# saturation_main.net
KiCad netlist of a schematic drawn in EAGLE
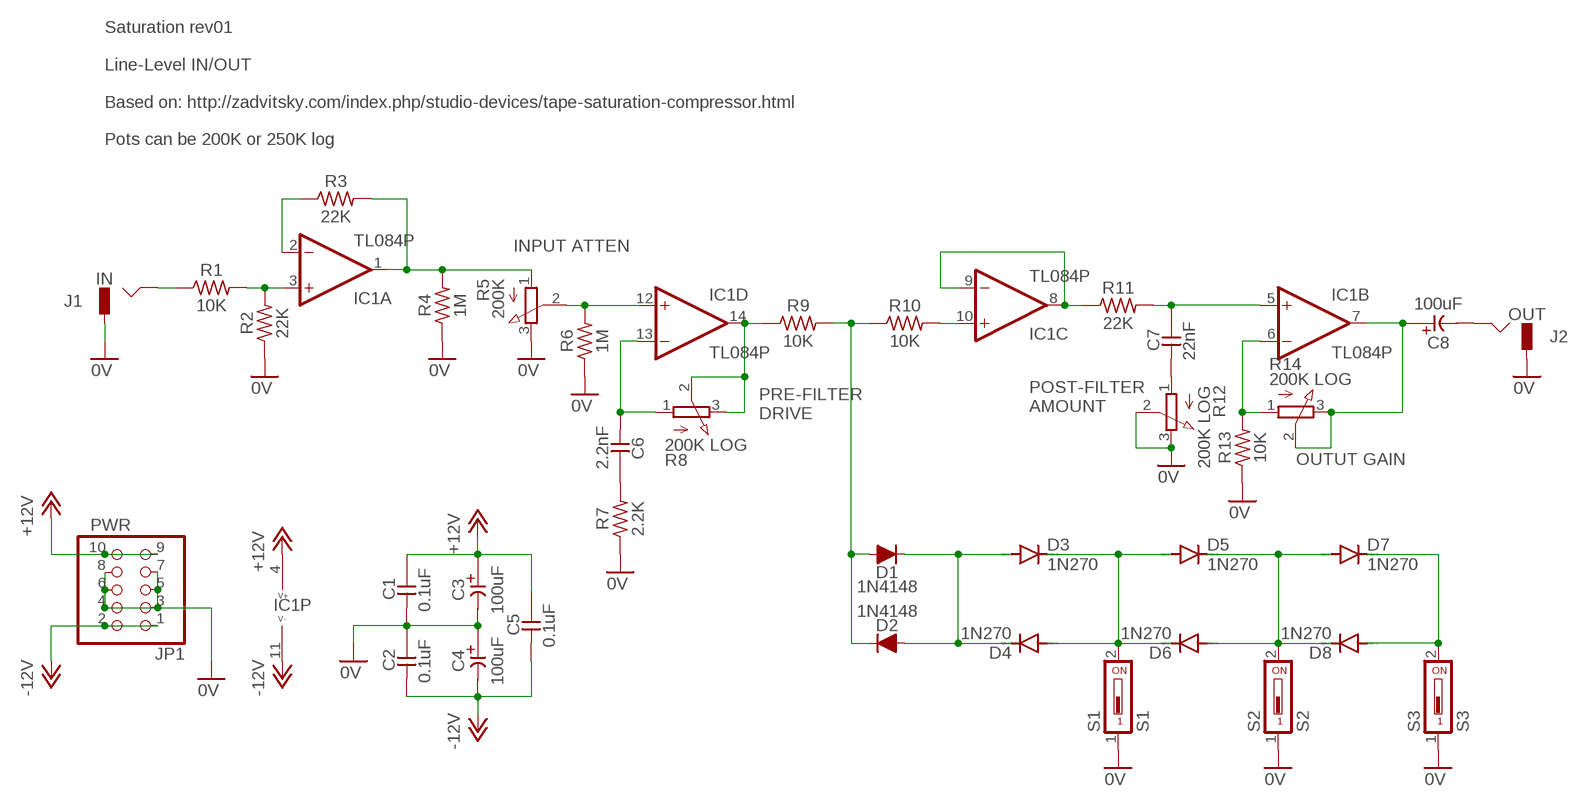
[diagram p0: schematic, sheet 1]

(export (version "E")
  (design (tool "Eeschema 10.0.6"))
  (components
    (comp (ref "C1")
      (value "0.1uF")
      (footprint "eagle-import:C025-024X044")
      (libsource (lib "eagle-import") (part "CC-US025-024X044"))
    )
    (comp (ref "C2")
      (value "0.1uF")
      (footprint "eagle-import:C025-024X044")
      (libsource (lib "eagle-import") (part "CC-US025-024X044"))
    )
    (comp (ref "C3")
      (value "100uF")
      (footprint "eagle-import:E5-8,5")
      (libsource (lib "eagle-import") (part "CE-USE5-8.5"))
    )
    (comp (ref "C4")
      (value "100uF")
      (footprint "eagle-import:E5-8,5")
      (libsource (lib "eagle-import") (part "CE-USE5-8.5"))
    )
    (comp (ref "C5")
      (value "0.1uF")
      (footprint "eagle-import:C025-024X044")
      (libsource (lib "eagle-import") (part "CC-US025-024X044"))
    )
    (comp (ref "C6")
      (value "2.2nF")
      (footprint "eagle-import:C025-024X044")
      (libsource (lib "eagle-import") (part "CC-US025-024X044"))
    )
    (comp (ref "C7")
      (value "22nF")
      (footprint "eagle-import:C025-024X044")
      (libsource (lib "eagle-import") (part "CC-US025-024X044"))
    )
    (comp (ref "C8")
      (value "100uF")
      (footprint "eagle-import:E5-8,5")
      (libsource (lib "eagle-import") (part "CE-USE5-8.5"))
    )
    (comp (ref "D1")
      (value "1N4148")
      (footprint "eagle-import:DO34-5")
      (libsource (lib "eagle-import") (part "1N4148"))
    )
    (comp (ref "D2")
      (value "1N4148")
      (footprint "eagle-import:DO34-5")
      (libsource (lib "eagle-import") (part "1N4148"))
    )
    (comp (ref "D3")
      (value "1N270")
      (footprint "eagle-import:DO07")
      (libsource (lib "eagle-import") (part "1N270"))
    )
    (comp (ref "D4")
      (value "1N270")
      (footprint "eagle-import:DO07")
      (libsource (lib "eagle-import") (part "1N270"))
    )
    (comp (ref "D5")
      (value "1N270")
      (footprint "eagle-import:DO07")
      (libsource (lib "eagle-import") (part "1N270"))
    )
    (comp (ref "D6")
      (value "1N270")
      (footprint "eagle-import:DO07")
      (libsource (lib "eagle-import") (part "1N270"))
    )
    (comp (ref "D7")
      (value "1N270")
      (footprint "eagle-import:DO07")
      (libsource (lib "eagle-import") (part "1N270"))
    )
    (comp (ref "D8")
      (value "1N270")
      (footprint "eagle-import:DO07")
      (libsource (lib "eagle-import") (part "1N270"))
    )
    (comp (ref "IC1")
      (value "TL084P")
      (footprint "eagle-import:DIL14")
      (libsource (lib "eagle-import") (part "TL084P"))
    )
    (comp (ref "J1")
      (value "IN")
      (footprint "eagle-import:JACK-M")
      (libsource (lib "eagle-import") (part "JACK-M"))
    )
    (comp (ref "J2")
      (value "OUT")
      (footprint "eagle-import:JACK-M")
      (libsource (lib "eagle-import") (part "JACK-M"))
    )
    (comp (ref "JP1")
      (value "PWR")
      (footprint "eagle-import:2X05")
      (libsource (lib "eagle-import") (part "PINHD-2X5"))
    )
    (comp (ref "R1")
      (value "10K")
      (footprint "eagle-import:0207_7")
      (libsource (lib "eagle-import") (part "R"))
    )
    (comp (ref "R2")
      (value "22K")
      (footprint "eagle-import:0207_7")
      (libsource (lib "eagle-import") (part "R"))
    )
    (comp (ref "R3")
      (value "22K")
      (footprint "eagle-import:0207_7")
      (libsource (lib "eagle-import") (part "R"))
    )
    (comp (ref "R4")
      (value "1M")
      (footprint "eagle-import:0207_7")
      (libsource (lib "eagle-import") (part "R"))
    )
    (comp (ref "R5")
      (value "200K")
      (footprint "eagle-import:3RP_1610N")
      (libsource (lib "eagle-import") (part "3RP/1610N"))
    )
    (comp (ref "R6")
      (value "1M")
      (footprint "eagle-import:0207_7")
      (libsource (lib "eagle-import") (part "R"))
    )
    (comp (ref "R7")
      (value "2.2K")
      (footprint "eagle-import:0207_7")
      (libsource (lib "eagle-import") (part "R"))
    )
    (comp (ref "R8")
      (value "200K LOG")
      (footprint "eagle-import:3RP_1610N")
      (libsource (lib "eagle-import") (part "3RP/1610N"))
    )
    (comp (ref "R9")
      (value "10K")
      (footprint "eagle-import:0207_7")
      (libsource (lib "eagle-import") (part "R"))
    )
    (comp (ref "R10")
      (value "10K")
      (footprint "eagle-import:0207_7")
      (libsource (lib "eagle-import") (part "R"))
    )
    (comp (ref "R11")
      (value "22K")
      (footprint "eagle-import:0207_7")
      (libsource (lib "eagle-import") (part "R"))
    )
    (comp (ref "R12")
      (value "200K LOG")
      (footprint "eagle-import:3RP_1610N")
      (libsource (lib "eagle-import") (part "3RP/1610N"))
    )
    (comp (ref "R13")
      (value "10K")
      (footprint "eagle-import:0207_7")
      (libsource (lib "eagle-import") (part "R"))
    )
    (comp (ref "R14")
      (value "200K LOG")
      (footprint "eagle-import:3RP_1610N")
      (libsource (lib "eagle-import") (part "3RP/1610N"))
    )
    (comp (ref "S1")
      (value "S1")
      (footprint "eagle-import:DS-01")
      (libsource (lib "eagle-import") (part "DS01"))
    )
    (comp (ref "S2")
      (value "S2")
      (footprint "eagle-import:DS-01")
      (libsource (lib "eagle-import") (part "DS01"))
    )
    (comp (ref "S3")
      (value "S3")
      (footprint "eagle-import:DS-01")
      (libsource (lib "eagle-import") (part "DS01"))
    )
  )
  (nets
    (net (code "1") (name "+12V") (class "Default")
      (node (ref "C1") (pin "1") (pinfunction "1_1") (pintype "passive"))
      (node (ref "C3") (pin "+") (pinfunction "+_+") (pintype "passive"))
      (node (ref "C5") (pin "1") (pinfunction "1_1") (pintype "passive"))
      (node (ref "IC1") (pin "4") (pinfunction "V+_4") (pintype "power_in"))
      (node (ref "JP1") (pin "10") (pinfunction "10_10") (pintype "passive"))
      (node (ref "JP1") (pin "9") (pinfunction "9_9") (pintype "passive"))
    )
    (net (code "2") (name "-12V") (class "Default")
      (node (ref "C2") (pin "2") (pinfunction "2_2") (pintype "passive"))
      (node (ref "C4") (pin "-") (pinfunction "-_-") (pintype "passive"))
      (node (ref "C5") (pin "2") (pinfunction "2_2") (pintype "passive"))
      (node (ref "IC1") (pin "11") (pinfunction "V-_11") (pintype "power_in"))
      (node (ref "JP1") (pin "1") (pinfunction "1_1") (pintype "passive"))
      (node (ref "JP1") (pin "2") (pinfunction "2_2") (pintype "passive"))
    )
    (net (code "3") (name "0V") (class "Default")
      (node (ref "C1") (pin "2") (pinfunction "2_2") (pintype "passive"))
      (node (ref "C2") (pin "1") (pinfunction "1_1") (pintype "passive"))
      (node (ref "C3") (pin "-") (pinfunction "-_-") (pintype "passive"))
      (node (ref "C4") (pin "+") (pinfunction "+_+") (pintype "passive"))
      (node (ref "J1") (pin "GND") (pinfunction "GND_GND") (pintype "bidirectional"))
      (node (ref "J2") (pin "GND") (pinfunction "GND_GND") (pintype "bidirectional"))
      (node (ref "JP1") (pin "3") (pinfunction "3_3") (pintype "passive"))
      (node (ref "JP1") (pin "4") (pinfunction "4_4") (pintype "passive"))
      (node (ref "JP1") (pin "5") (pinfunction "5_5") (pintype "passive"))
      (node (ref "JP1") (pin "6") (pinfunction "6_6") (pintype "passive"))
      (node (ref "JP1") (pin "7") (pinfunction "7_7") (pintype "passive"))
      (node (ref "JP1") (pin "8") (pinfunction "8_8") (pintype "passive"))
      (node (ref "R12") (pin "2") (pinfunction "S_2") (pintype "passive"))
      (node (ref "R12") (pin "3") (pinfunction "E_3") (pintype "passive"))
      (node (ref "R13") (pin "1") (pinfunction "1_1") (pintype "passive"))
      (node (ref "R2") (pin "1") (pinfunction "1_1") (pintype "passive"))
      (node (ref "R4") (pin "1") (pinfunction "1_1") (pintype "passive"))
      (node (ref "R5") (pin "3") (pinfunction "E_3") (pintype "passive"))
      (node (ref "R6") (pin "1") (pinfunction "1_1") (pintype "passive"))
      (node (ref "R7") (pin "1") (pinfunction "1_1") (pintype "passive"))
      (node (ref "S1") (pin "1") (pinfunction "1_1") (pintype "passive"))
      (node (ref "S2") (pin "1") (pinfunction "1_1") (pintype "passive"))
      (node (ref "S3") (pin "1") (pinfunction "1_1") (pintype "passive"))
    )
    (net (code "4") (name "Net-(C6-Pad1)") (class "Default")
      (node (ref "C6") (pin "1") (pinfunction "1_1") (pintype "passive"))
      (node (ref "R7") (pin "2") (pinfunction "2_2") (pintype "passive"))
    )
    (net (code "5") (name "Net-(C8-Pad-)") (class "Default")
      (node (ref "C8") (pin "-") (pinfunction "-_-") (pintype "passive"))
      (node (ref "J2") (pin "HOT") (pinfunction "HOT_HOT") (pintype "bidirectional"))
    )
    (net (code "6") (name "Net-(D1-PadA)") (class "Default")
      (node (ref "D1") (pin "A") (pinfunction "A_A") (pintype "passive"))
      (node (ref "D2") (pin "C") (pinfunction "C_C") (pintype "passive"))
      (node (ref "R10") (pin "1") (pinfunction "1_1") (pintype "passive"))
      (node (ref "R9") (pin "2") (pinfunction "2_2") (pintype "passive"))
    )
    (net (code "7") (name "Net-(D1-PadC)") (class "Default")
      (node (ref "D1") (pin "C") (pinfunction "C_C") (pintype "passive"))
      (node (ref "D2") (pin "A") (pinfunction "A_A") (pintype "passive"))
      (node (ref "D3") (pin "A") (pinfunction "A_A") (pintype "passive"))
      (node (ref "D4") (pin "C") (pinfunction "C_C") (pintype "passive"))
    )
    (net (code "8") (name "Net-(D3-PadC)") (class "Default")
      (node (ref "D3") (pin "C") (pinfunction "C_C") (pintype "passive"))
      (node (ref "D4") (pin "A") (pinfunction "A_A") (pintype "passive"))
      (node (ref "D5") (pin "A") (pinfunction "A_A") (pintype "passive"))
      (node (ref "D6") (pin "C") (pinfunction "C_C") (pintype "passive"))
      (node (ref "S1") (pin "2") (pinfunction "2_2") (pintype "passive"))
    )
    (net (code "9") (name "Net-(D5-PadC)") (class "Default")
      (node (ref "D5") (pin "C") (pinfunction "C_C") (pintype "passive"))
      (node (ref "D6") (pin "A") (pinfunction "A_A") (pintype "passive"))
      (node (ref "D7") (pin "A") (pinfunction "A_A") (pintype "passive"))
      (node (ref "D8") (pin "C") (pinfunction "C_C") (pintype "passive"))
      (node (ref "S2") (pin "2") (pinfunction "2_2") (pintype "passive"))
    )
    (net (code "10") (name "Net-(D7-PadC)") (class "Default")
      (node (ref "D7") (pin "C") (pinfunction "C_C") (pintype "passive"))
      (node (ref "D8") (pin "A") (pinfunction "A_A") (pintype "passive"))
      (node (ref "S3") (pin "2") (pinfunction "2_2") (pintype "passive"))
    )
    (net (code "11") (name "Net-(IC1A-+IN)") (class "Default")
      (node (ref "IC1") (pin "3") (pinfunction "+IN_3") (pintype "input"))
      (node (ref "R1") (pin "2") (pinfunction "2_2") (pintype "passive"))
      (node (ref "R2") (pin "2") (pinfunction "2_2") (pintype "passive"))
    )
    (net (code "12") (name "Net-(IC1A--IN)") (class "Default")
      (node (ref "IC1") (pin "2") (pinfunction "-IN_2") (pintype "input"))
      (node (ref "R3") (pin "1") (pinfunction "1_1") (pintype "passive"))
    )
    (net (code "13") (name "Net-(IC1A-OUT)") (class "Default")
      (node (ref "IC1") (pin "1") (pinfunction "OUT_1") (pintype "output"))
      (node (ref "R3") (pin "2") (pinfunction "2_2") (pintype "passive"))
      (node (ref "R4") (pin "2") (pinfunction "2_2") (pintype "passive"))
      (node (ref "R5") (pin "1") (pinfunction "A_1") (pintype "passive"))
    )
    (net (code "14") (name "Net-(IC1B-+IN)") (class "Default")
      (node (ref "C7") (pin "1") (pinfunction "1_1") (pintype "passive"))
      (node (ref "IC1") (pin "5") (pinfunction "+IN_5") (pintype "input"))
      (node (ref "R11") (pin "2") (pinfunction "2_2") (pintype "passive"))
    )
    (net (code "15") (name "Net-(IC1B--IN)") (class "Default")
      (node (ref "IC1") (pin "6") (pinfunction "-IN_6") (pintype "input"))
      (node (ref "R13") (pin "2") (pinfunction "2_2") (pintype "passive"))
      (node (ref "R14") (pin "1") (pinfunction "A_1") (pintype "passive"))
    )
    (net (code "16") (name "Net-(IC1B-OUT)") (class "Default")
      (node (ref "C8") (pin "+") (pinfunction "+_+") (pintype "passive"))
      (node (ref "IC1") (pin "7") (pinfunction "OUT_7") (pintype "output"))
      (node (ref "R14") (pin "2") (pinfunction "S_2") (pintype "passive"))
      (node (ref "R14") (pin "3") (pinfunction "E_3") (pintype "passive"))
    )
    (net (code "17") (name "Net-(IC1C-+IN)") (class "Default")
      (node (ref "IC1") (pin "10") (pinfunction "+IN_10") (pintype "input"))
      (node (ref "R10") (pin "2") (pinfunction "2_2") (pintype "passive"))
    )
    (net (code "18") (name "Net-(IC1C--IN)") (class "Default")
      (node (ref "IC1") (pin "8") (pinfunction "OUT_8") (pintype "output"))
      (node (ref "IC1") (pin "9") (pinfunction "-IN_9") (pintype "input"))
      (node (ref "R11") (pin "1") (pinfunction "1_1") (pintype "passive"))
    )
    (net (code "19") (name "Net-(IC1D-+IN)") (class "Default")
      (node (ref "IC1") (pin "12") (pinfunction "+IN_12") (pintype "input"))
      (node (ref "R5") (pin "2") (pinfunction "S_2") (pintype "passive"))
      (node (ref "R6") (pin "2") (pinfunction "2_2") (pintype "passive"))
    )
    (net (code "20") (name "Net-(IC1D--IN)") (class "Default")
      (node (ref "C6") (pin "2") (pinfunction "2_2") (pintype "passive"))
      (node (ref "IC1") (pin "13") (pinfunction "-IN_13") (pintype "input"))
      (node (ref "R8") (pin "1") (pinfunction "A_1") (pintype "passive"))
    )
    (net (code "21") (name "Net-(IC1D-OUT)") (class "Default")
      (node (ref "IC1") (pin "14") (pinfunction "OUT_14") (pintype "output"))
      (node (ref "R8") (pin "2") (pinfunction "S_2") (pintype "passive"))
      (node (ref "R8") (pin "3") (pinfunction "E_3") (pintype "passive"))
      (node (ref "R9") (pin "1") (pinfunction "1_1") (pintype "passive"))
    )
    (net (code "22") (name "Net-(J1-PadHOT)") (class "Default")
      (node (ref "J1") (pin "HOT") (pinfunction "HOT_HOT") (pintype "bidirectional"))
      (node (ref "R1") (pin "1") (pinfunction "1_1") (pintype "passive"))
    )
    (net (code "23") (name "Net-(R12-A)") (class "Default")
      (node (ref "C7") (pin "2") (pinfunction "2_2") (pintype "passive"))
      (node (ref "R12") (pin "1") (pinfunction "A_1") (pintype "passive"))
    )
  )
)
